# MCU_main_2.net
KiCad netlist of a schematic drawn in Altium Designer
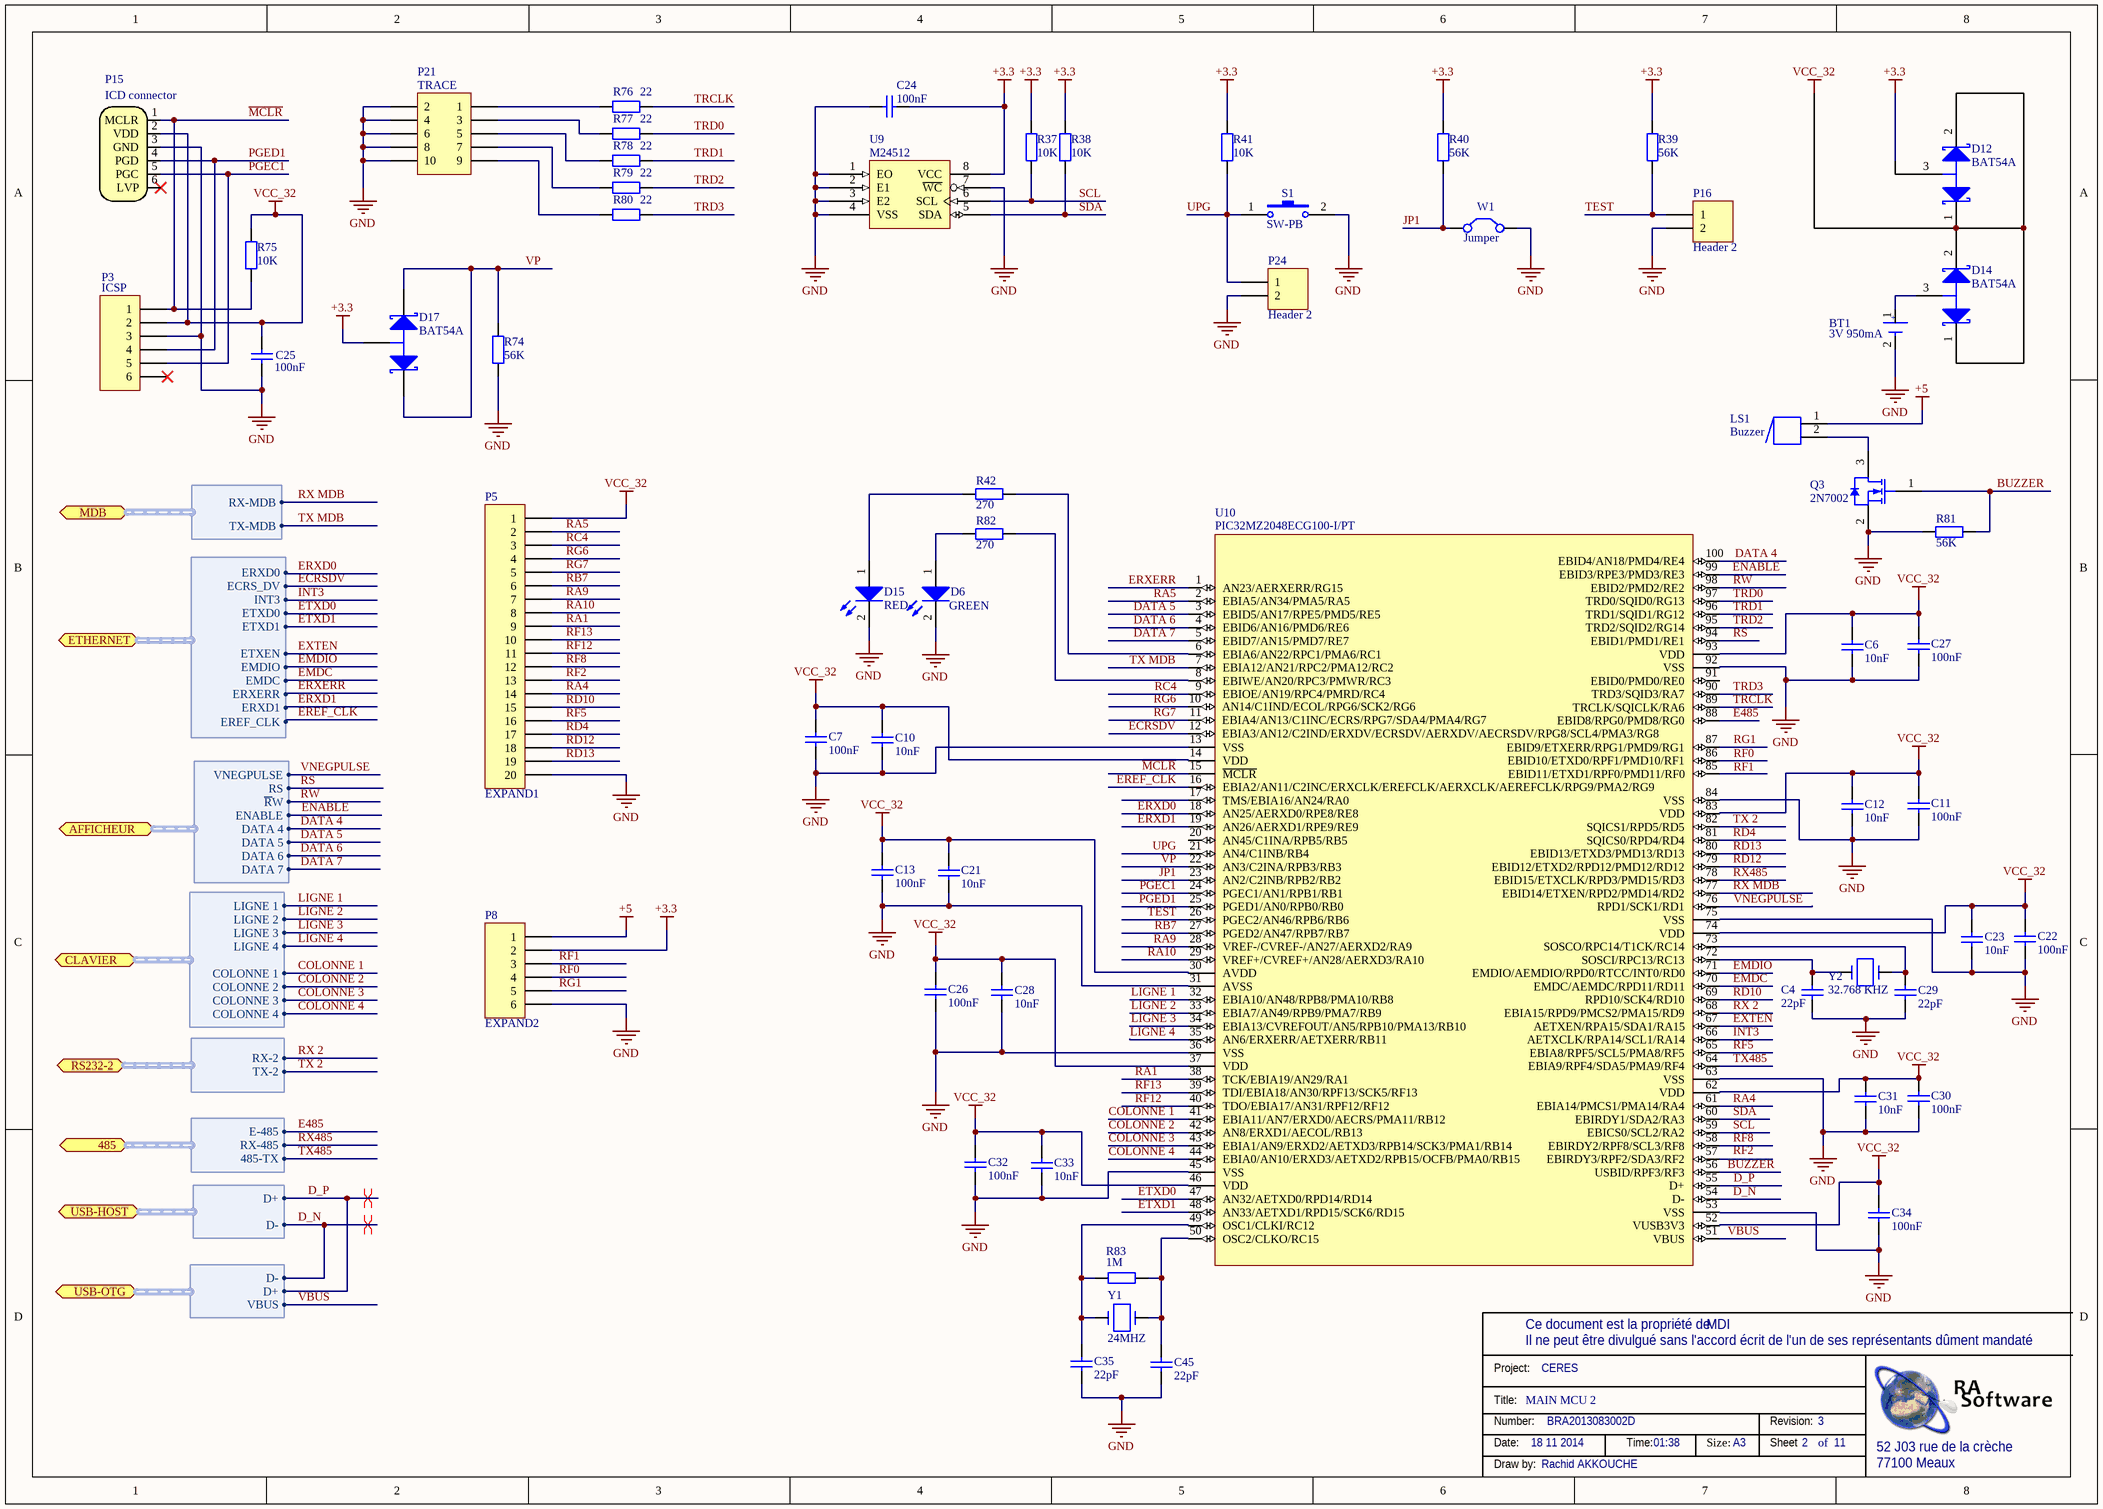
[diagram p0: MCU main_2.SchDoc]

(export (version "E")
  (design (tool "Eeschema 10.0.6"))
  (components
    (comp (ref "BT1")
      (value "3V 950mA")
      (footprint "CR2477+SMTU")
      (fields (field (name "MANUFACTURER") "RENATA") (field (name "MANUFACTURER PART NUMBER") "CR2477N"))
      (libsource (lib "UTIL_Library") (part "Batterie"))
    )
    (comp (ref "C4")
      (value "22pF")
      (footprint "C0805")
      (description "Capacitor")
      (fields
        (field (name "MANUFACTURER") "YAGEO")
        (field (name "MANUFACTURER PART NUMBER") "CC0805JRNPO9BN220")
      )
      (libsource (lib "BRA") (part "Cap 0805 22pF"))
    )
    (comp (ref "C6")
      (value "10nF")
      (footprint "C0805")
      (description "Capacitor")
      (fields (field (name "MANUFACTURER") "AVX") (field (name "MANUFACTURER PART NUMBER") "0402YC103KAT2A"))
      (libsource (lib "BRA") (part "Cap 0805 10nF"))
    )
    (comp (ref "C7")
      (value "100nF")
      (footprint "C0805")
      (description "Capacitor")
      (fields
        (field (name "MANUFACTURER") "MULTICOMP")
        (field (name "MANUFACTURER PART NUMBER") "MCCA000296")
      )
      (libsource (lib "BRA") (part "Cap 0805 100nF"))
    )
    (comp (ref "C10")
      (value "10nF")
      (footprint "C0805")
      (description "Capacitor")
      (fields (field (name "MANUFACTURER") "AVX") (field (name "MANUFACTURER PART NUMBER") "0402YC103KAT2A"))
      (libsource (lib "BRA") (part "Cap 0805 10nF"))
    )
    (comp (ref "C11")
      (value "100nF")
      (footprint "C0805")
      (description "Capacitor")
      (fields
        (field (name "MANUFACTURER") "MULTICOMP")
        (field (name "MANUFACTURER PART NUMBER") "MCCA000296")
      )
      (libsource (lib "BRA") (part "Cap 0805 100nF"))
    )
    (comp (ref "C12")
      (value "10nF")
      (footprint "C0805")
      (description "Capacitor")
      (fields (field (name "MANUFACTURER") "AVX") (field (name "MANUFACTURER PART NUMBER") "0402YC103KAT2A"))
      (libsource (lib "BRA") (part "Cap 0805 10nF"))
    )
    (comp (ref "C13")
      (value "100nF")
      (footprint "C0805")
      (description "Capacitor")
      (fields
        (field (name "MANUFACTURER") "MULTICOMP")
        (field (name "MANUFACTURER PART NUMBER") "MCCA000296")
      )
      (libsource (lib "BRA") (part "Cap 0805 100nF"))
    )
    (comp (ref "C21")
      (value "10nF")
      (footprint "C0805")
      (description "Capacitor")
      (fields (field (name "MANUFACTURER") "AVX") (field (name "MANUFACTURER PART NUMBER") "0402YC103KAT2A"))
      (libsource (lib "BRA") (part "Cap 0805 10nF"))
    )
    (comp (ref "C22")
      (value "100nF")
      (footprint "C0805")
      (description "Capacitor")
      (fields
        (field (name "MANUFACTURER") "MULTICOMP")
        (field (name "MANUFACTURER PART NUMBER") "MCCA000296")
      )
      (libsource (lib "BRA") (part "Cap 0805 100nF"))
    )
    (comp (ref "C23")
      (value "10nF")
      (footprint "C0805")
      (description "Capacitor")
      (fields (field (name "MANUFACTURER") "AVX") (field (name "MANUFACTURER PART NUMBER") "0402YC103KAT2A"))
      (libsource (lib "BRA") (part "Cap 0805 10nF"))
    )
    (comp (ref "C24")
      (value "100nF")
      (footprint "C0805")
      (description "Capacitor")
      (fields
        (field (name "MANUFACTURER") "MULTICOMP")
        (field (name "MANUFACTURER PART NUMBER") "MCCA000296")
      )
      (libsource (lib "BRA") (part "Cap 0805 100nF"))
    )
    (comp (ref "C25")
      (value "100nF")
      (footprint "C0805")
      (description "Capacitor")
      (fields
        (field (name "MANUFACTURER") "MULTICOMP")
        (field (name "MANUFACTURER PART NUMBER") "MCCA000296")
      )
      (libsource (lib "BRA") (part "Cap 0805 100nF"))
    )
    (comp (ref "C26")
      (value "100nF")
      (footprint "C0805")
      (description "Capacitor")
      (fields
        (field (name "MANUFACTURER") "MULTICOMP")
        (field (name "MANUFACTURER PART NUMBER") "MCCA000296")
      )
      (libsource (lib "BRA") (part "Cap 0805 100nF"))
    )
    (comp (ref "C27")
      (value "100nF")
      (footprint "C0805")
      (description "Capacitor")
      (fields
        (field (name "MANUFACTURER") "MULTICOMP")
        (field (name "MANUFACTURER PART NUMBER") "MCCA000296")
      )
      (libsource (lib "BRA") (part "Cap 0805 100nF"))
    )
    (comp (ref "C28")
      (value "10nF")
      (footprint "C0805")
      (description "Capacitor")
      (fields (field (name "MANUFACTURER") "AVX") (field (name "MANUFACTURER PART NUMBER") "0402YC103KAT2A"))
      (libsource (lib "BRA") (part "Cap 0805 10nF"))
    )
    (comp (ref "C29")
      (value "22pF")
      (footprint "C0805")
      (description "Capacitor")
      (fields
        (field (name "MANUFACTURER") "YAGEO")
        (field (name "MANUFACTURER PART NUMBER") "CC0805JRNPO9BN220")
      )
      (libsource (lib "BRA") (part "Cap 0805 22pF"))
    )
    (comp (ref "C30")
      (value "100nF")
      (footprint "C0805")
      (description "Capacitor")
      (fields
        (field (name "MANUFACTURER") "MULTICOMP")
        (field (name "MANUFACTURER PART NUMBER") "MCCA000296")
      )
      (libsource (lib "BRA") (part "Cap 0805 100nF"))
    )
    (comp (ref "C31")
      (value "10nF")
      (footprint "C0805")
      (description "Capacitor")
      (fields (field (name "MANUFACTURER") "AVX") (field (name "MANUFACTURER PART NUMBER") "0402YC103KAT2A"))
      (libsource (lib "BRA") (part "Cap 0805 10nF"))
    )
    (comp (ref "C32")
      (value "100nF")
      (footprint "C0805")
      (description "Capacitor")
      (fields
        (field (name "MANUFACTURER") "MULTICOMP")
        (field (name "MANUFACTURER PART NUMBER") "MCCA000296")
      )
      (libsource (lib "BRA") (part "Cap 0805 100nF"))
    )
    (comp (ref "C33")
      (value "10nF")
      (footprint "C0805")
      (description "Capacitor")
      (fields (field (name "MANUFACTURER") "AVX") (field (name "MANUFACTURER PART NUMBER") "0402YC103KAT2A"))
      (libsource (lib "BRA") (part "Cap 0805 10nF"))
    )
    (comp (ref "C34")
      (value "100nF")
      (footprint "C0805")
      (description "Capacitor")
      (fields
        (field (name "MANUFACTURER") "MULTICOMP")
        (field (name "MANUFACTURER PART NUMBER") "MCCA000296")
      )
      (libsource (lib "BRA") (part "Cap 0805 100nF"))
    )
    (comp (ref "C35")
      (value "22pF")
      (footprint "C0805")
      (description "Capacitor")
      (fields
        (field (name "MANUFACTURER") "YAGEO")
        (field (name "MANUFACTURER PART NUMBER") "CC0805JRNPO9BN220")
      )
      (libsource (lib "BRA") (part "Cap 0805 22pF"))
    )
    (comp (ref "C45")
      (value "22pF")
      (footprint "C0805")
      (description "Capacitor")
      (fields
        (field (name "MANUFACTURER") "YAGEO")
        (field (name "MANUFACTURER PART NUMBER") "CC0805JRNPO9BN220")
      )
      (libsource (lib "BRA") (part "Cap 0805 22pF"))
    )
    (comp (ref "D6")
      (value "HSMG-C191")
      (footprint "SYLANN:0603-LEDR")
      (description "Surface Mount Chip LED, Green")
      (fields (field (name "COULEUR") "GREEN"))
      (libsource (lib "Avago Optoelectronic LED") (part "HSMH-C190"))
    )
    (comp (ref "D12")
      (value "BAT54A")
      (footprint "SOT23")
      (description "Schottky Barrier Double Diode")
      (fields (field (name "MANUFACTURER") "FAIRCHILD SEMICONDUCTOR"))
      (libsource (lib "Philips Discrete Diode - Schottky") (part "BAT54A"))
    )
    (comp (ref "D14")
      (value "BAT54A")
      (footprint "SOT23")
      (description "Schottky Barrier Double Diode")
      (fields (field (name "MANUFACTURER") "FAIRCHILD SEMICONDUCTOR"))
      (libsource (lib "Philips Discrete Diode - Schottky") (part "BAT54A"))
    )
    (comp (ref "D15")
      (value "HSMH-C190")
      (footprint "SYLANN:0603-LEDR")
      (description "Surface Mount Chip LED, Red")
      (fields
        (field (name "MANUFACTURER") "AVAGO TECHNOLOGIES")
        (field (name "MANUFACTURER PART NUMBER") "HSMH-C190.")
        (field (name "COULEUR") "RED")
        (field (name "LONGUEUR/HAUTEUR") "1.6")
      )
      (libsource (lib "Avago Optoelectronic LED") (part "HSMH-C190"))
    )
    (comp (ref "D17")
      (value "BAT54A")
      (footprint "SOT23")
      (description "Schottky Barrier Double Diode")
      (fields (field (name "MANUFACTURER") "FAIRCHILD SEMICONDUCTOR"))
      (libsource (lib "") (part "BAT54A_1"))
    )
    (comp (ref "LS1")
      (value "Buzzer")
      (footprint "Buzzer ABI-017-RC")
      (description "Magnetic Transducer Buzzer")
      (fields
        (field (name "MANUFACTURER") "PRO SIGNAL")
        (field (name "MANUFACTURER PART NUMBER") "ABI-017-RC")
        (field (name "HAUTEUR, DIMENSION EXTERNE") "12.8")
        (field (name "HAUTEUR") "12.8")
        (field (name "LONGUEUR/HAUTEUR") "12.8")
      )
      (libsource (lib "Miscellaneous Devices") (part "Buzzer"))
    )
    (comp (ref "P3")
      (value "M20-8770642")
      (footprint "M20_1X6")
      (description "Header, 6-Pin")
      (fields (field (name "MANUFACTURER") "HARWIN") (field (name "ALTIUM_UNNAMED_1") "ICSP"))
      (libsource (lib "Miscellaneous Connectors") (part "Header 6"))
    )
    (comp (ref "P5")
      (value "EXPAND1")
      (footprint "M20-2X10")
      (description "Header, 20-Pin")
      (fields (field (name "PUBLISHER") "Altium Limited"))
      (libsource (lib "Miscellaneous Connectors") (part "Header 20"))
    )
    (comp (ref "P8")
      (value "EXPAND2")
      (footprint "M20_1X6")
      (description "Header, 6-Pin")
      (fields (field (name "PUBLISHER") "Altium Limited"))
      (libsource (lib "Miscellaneous Connectors") (part "Header 6"))
    )
    (comp (ref "P15")
      (value "ICD connector")
      (footprint "TC2030")
      (description "Conector par ICD")
      (libsource (lib "TC2030") (part "TC2030-MCP-NL"))
    )
    (comp (ref "P16")
      (value "Header 2")
      (footprint "M20_1X2")
      (description "Header, 2-Pin")
      (fields
        (field (name "MANUFACTURER") "HARWIN")
        (field (name "MANUFACTURER PART NUMBER") "M20-8770242")
        (field (name "PUBLISHER") "Altium Limited")
      )
      (libsource (lib "Miscellaneous Connectors") (part "Header 2"))
    )
    (comp (ref "P21")
      (value "M20-8760542")
      (footprint "HE10_10PTS_CMS")
      (description "Header, 5-Pin, Dual row")
      (fields (field (name "ALTIUM_UNNAMED_1") "TRACE") (field (name "MANUFACTURER") "HARWIN"))
      (libsource (lib "Miscellaneous Connectors") (part "Header 5X2"))
    )
    (comp (ref "P24")
      (value "Header 2")
      (footprint "M20_1X2")
      (description "Header, 2-Pin")
      (fields
        (field (name "MANUFACTURER") "HARWIN")
        (field (name "MANUFACTURER PART NUMBER") "M20-8770242")
        (field (name "PUBLISHER") "Altium Limited")
      )
      (libsource (lib "Miscellaneous Connectors") (part "Header 2"))
    )
    (comp (ref "Q3")
      (value "2N7002")
      (footprint "SOT23")
      (description "N-channel Enhancement Mode Field-effect Transistor")
      (fields (field (name "MANUFACTURER") "STMICROELECTRONICS") (field (name "PUBLISHER") "Altium Limited"))
      (libsource (lib "Philips Discrete MOSFET - Low Power") (part "2N7002"))
    )
    (comp (ref "R37")
      (value "10K")
      (footprint "R0805")
      (description "Resistor")
      (fields
        (field (name "MANUFACTURER") "MULTICOMP")
        (field (name "MANUFACTURER PART NUMBER") "MC0.1W08051%10KFR")
      )
      (libsource (lib "BRA") (part "Resistor 0805 10K"))
    )
    (comp (ref "R38")
      (value "10K")
      (footprint "R0805")
      (description "Resistor")
      (fields
        (field (name "MANUFACTURER") "MULTICOMP")
        (field (name "MANUFACTURER PART NUMBER") "MC0.1W08051%10KFR")
      )
      (libsource (lib "BRA") (part "Resistor 0805 10K"))
    )
    (comp (ref "R39")
      (value "56K")
      (footprint "R0805")
      (description "Resistor")
      (fields
        (field (name "MANUFACTURER") "MULTICOMP")
        (field (name "MANUFACTURER PART NUMBER") "MC0.1W08051%56KFR")
      )
      (libsource (lib "BRA") (part "Resistor 0805 56K"))
    )
    (comp (ref "R40")
      (value "56K")
      (footprint "R0805")
      (description "Resistor")
      (fields
        (field (name "MANUFACTURER") "MULTICOMP")
        (field (name "MANUFACTURER PART NUMBER") "MC0.1W08051%56KFR")
      )
      (libsource (lib "BRA") (part "Resistor 0805 56K"))
    )
    (comp (ref "R41")
      (value "10K")
      (footprint "R0805")
      (description "Resistor")
      (fields
        (field (name "MANUFACTURER") "MULTICOMP")
        (field (name "MANUFACTURER PART NUMBER") "MC0.1W08051%10KFR")
      )
      (libsource (lib "BRA") (part "Resistor 0805 10K"))
    )
    (comp (ref "R42")
      (value "270")
      (footprint "R0805")
      (description "Resistor")
      (fields
        (field (name "MANUFACTURER") "MULTICOMP")
        (field (name "MANUFACTURER PART NUMBER") "MC0.1W08051%1KFR")
      )
      (libsource (lib "BRA") (part "Resistor 0805 1K"))
    )
    (comp (ref "R74")
      (value "56K")
      (footprint "R0805")
      (description "Resistor")
      (fields
        (field (name "MANUFACTURER") "MULTICOMP")
        (field (name "MANUFACTURER PART NUMBER") "MC0.1W08051%56KFR")
      )
      (libsource (lib "") (part "Resistor 0805 56K_1"))
    )
    (comp (ref "R75")
      (value "10K")
      (footprint "R0805")
      (description "Resistor")
      (fields
        (field (name "MANUFACTURER") "MULTICOMP")
        (field (name "MANUFACTURER PART NUMBER") "MC0.1W08051%10KFR")
      )
      (libsource (lib "BRA") (part "Resistor 0805 10K"))
    )
    (comp (ref "R76")
      (value "22")
      (footprint "R0805")
      (description "Resistor")
      (fields
        (field (name "MANUFACTURER") "MULTICOMP")
        (field (name "MANUFACTURER PART NUMBER") "MC01W0805122R")
      )
      (libsource (lib "BRA") (part "Resistor 0805 22"))
    )
    (comp (ref "R77")
      (value "22")
      (footprint "R0805")
      (description "Resistor")
      (fields
        (field (name "MANUFACTURER") "MULTICOMP")
        (field (name "MANUFACTURER PART NUMBER") "MC01W0805122R")
      )
      (libsource (lib "BRA") (part "Resistor 0805 22"))
    )
    (comp (ref "R78")
      (value "22")
      (footprint "R0805")
      (description "Resistor")
      (fields
        (field (name "MANUFACTURER") "MULTICOMP")
        (field (name "MANUFACTURER PART NUMBER") "MC01W0805122R")
      )
      (libsource (lib "BRA") (part "Resistor 0805 22"))
    )
    (comp (ref "R79")
      (value "22")
      (footprint "R0805")
      (description "Resistor")
      (fields
        (field (name "MANUFACTURER") "MULTICOMP")
        (field (name "MANUFACTURER PART NUMBER") "MC01W0805122R")
      )
      (libsource (lib "BRA") (part "Resistor 0805 22"))
    )
    (comp (ref "R80")
      (value "22")
      (footprint "R0805")
      (description "Resistor")
      (fields
        (field (name "MANUFACTURER") "MULTICOMP")
        (field (name "MANUFACTURER PART NUMBER") "MC01W0805122R")
      )
      (libsource (lib "BRA") (part "Resistor 0805 22"))
    )
    (comp (ref "R81")
      (value "56K")
      (footprint "R0805")
      (description "Resistor")
      (fields
        (field (name "MANUFACTURER") "MULTICOMP")
        (field (name "MANUFACTURER PART NUMBER") "MC0.1W08051%56KFR")
      )
      (libsource (lib "BRA") (part "Resistor 0805 56K"))
    )
    (comp (ref "R82")
      (value "270")
      (footprint "R0805")
      (description "Resistor")
      (fields
        (field (name "MANUFACTURER") "MULTICOMP")
        (field (name "MANUFACTURER PART NUMBER") "MC0.1W08051%1KFR")
      )
      (libsource (lib "BRA") (part "Resistor 0805 1K"))
    )
    (comp (ref "R83")
      (value "1M")
      (footprint "R0805")
      (description "Resistor")
      (libsource (lib "BRA") (part "Resistor 0805 1M"))
    )
    (comp (ref "S1")
      (value "SW-PB")
      (footprint "EVQQ2Y03W")
      (description "Switch")
      (fields
        (field (name "MANUFACTURER") "PANASONIC")
        (field (name "MANUFACTURER PART NUMBER") "EVQQ2Y03W")
        (field (name "PUBLISHER") "Altium Limited")
      )
      (libsource (lib "Miscellaneous Devices") (part "SW-PB"))
    )
    (comp (ref "U9")
      (value "M24512")
      (footprint "SOIC8")
      (description "EEPROM 512K I2C")
      (fields
        (field (name "MANUFACTURER") "STMICROELECTRONICS")
        (field (name "MANUFACTURER PART NUMBER") "M24512-WMN6P")
      )
      (libsource (lib "BRA") (part "M24512-MN"))
    )
    (comp (ref "U10")
      (value "PIC32MZ2048ECG100-I/PT")
      (footprint "TQFP100pt")
      (description "PIC32MZ2048ECG100")
      (fields (field (name "MANUFACTURER") "Microchip Technology"))
      (libsource (lib "BRA") (part "PIC32MZ Embedded Connectivity"))
    )
    (comp (ref "W1")
      (value "Jumper")
      (footprint "M20_1X2")
      (description "Jumper Wire")
      (fields
        (field (name "MANUFACTURER") "HARWIN")
        (field (name "MANUFACTURER PART NUMBER") "M20-8770242")
        (field (name "PUBLISHER") "Altium Limited")
      )
      (libsource (lib "Miscellaneous Devices") (part "Jumper"))
    )
    (comp (ref "Y1")
      (value "24MHZ")
      (footprint "HC49SD")
      (description "QUARTZ 24MHZ")
      (fields (field (name "MANUFACTURER") "YIC"))
      (libsource (lib "BRA") (part "CRYSTAL 24MHZ"))
    )
    (comp (ref "Y2")
      (value "32.768 KHZ")
      (footprint "86SMX")
      (fields
        (field (name "MANUFACTURER") "FOX ELECTRONICS")
        (field (name "MANUFACTURER PART NUMBER") "FPXLF080-20")
      )
      (libsource (lib "UTIL_Library") (part "CRYSTAL2"))
    )
  )
  (nets
    (net (code "10") (name "+3.3") (class "Default")
      (node (ref "C24") (pin "1") (pinfunction "1_1") (pintype "passive"))
      (node (ref "D12") (pin "3") (pinfunction "A_3") (pintype "passive"))
      (node (ref "D17") (pin "3") (pinfunction "A_3") (pintype "passive"))
      (node (ref "P8") (pin "2") (pinfunction "2_2") (pintype "passive"))
      (node (ref "R37") (pin "2") (pinfunction "2_2") (pintype "passive"))
      (node (ref "R38") (pin "2") (pinfunction "2_2") (pintype "passive"))
      (node (ref "R39") (pin "2") (pinfunction "2_2") (pintype "passive"))
      (node (ref "R40") (pin "2") (pinfunction "2_2") (pintype "passive"))
      (node (ref "R41") (pin "2") (pinfunction "2_2") (pintype "passive"))
      (node (ref "U9") (pin "8") (pinfunction "VCC_8") (pintype "power_in"))
    )
    (net (code "11") (name "+5") (class "Default")
      (node (ref "LS1") (pin "1") (pinfunction "1_1") (pintype "passive"))
      (node (ref "P8") (pin "1") (pinfunction "1_1") (pintype "passive"))
    )
    (net (code "12") (name "/BUZZER") (class "Default")
      (node (ref "Q3") (pin "1") (pinfunction "G_1") (pintype "passive"))
      (node (ref "R81") (pin "2") (pinfunction "2_2") (pintype "passive"))
      (node (ref "U10") (pin "56") (pinfunction "USBID/RPF3/RF3_56") (pintype "bidirectional"))
    )
    (net (code "13") (name "/COLONNE 1") (class "Default")
      (node (ref "U10") (pin "41") (pinfunction "EBIA11/AN7/ERXD0/AECRS/PMA11/RB12_41") (pintype "bidirectional"))
    )
    (net (code "14") (name "/COLONNE 2") (class "Default")
      (node (ref "U10") (pin "42") (pinfunction "AN8/ERXD1/AECOL/RB13_42") (pintype "bidirectional"))
    )
    (net (code "15") (name "/COLONNE 3") (class "Default")
      (node (ref "U10") (pin "43") (pinfunction "EBIA1/AN9/ERXD2/AETXD3/RPB14/SCK3/PMA1/RB14_43") (pintype "bidirectional"))
    )
    (net (code "16") (name "/COLONNE 4") (class "Default")
      (node (ref "U10") (pin "44") (pinfunction "EBIA0/AN10/ERXD3/AETXD2/RPB15/OCFB/PMA0/RB15_44") (pintype "bidirectional"))
    )
    (net (code "17") (name "/DATA 4") (class "Default")
      (node (ref "U10") (pin "100") (pinfunction "EBID4/AN18/PMD4/RE4_100") (pintype "bidirectional"))
    )
    (net (code "18") (name "/DATA 5") (class "Default")
      (node (ref "U10") (pin "3") (pinfunction "EBID5/AN17/RPE5/PMD5/RE5_3") (pintype "bidirectional"))
    )
    (net (code "19") (name "/DATA 6") (class "Default")
      (node (ref "U10") (pin "4") (pinfunction "EBID6/AN16/PMD6/RE6_4") (pintype "bidirectional"))
    )
    (net (code "20") (name "/DATA 7") (class "Default")
      (node (ref "U10") (pin "5") (pinfunction "EBID7/AN15/PMD7/RE7_5") (pintype "bidirectional"))
    )
    (net (code "21") (name "/D_N") (class "Default")
      (node (ref "U10") (pin "54") (pinfunction "D-_54") (pintype "bidirectional"))
    )
    (net (code "22") (name "/D_P") (class "Default")
      (node (ref "U10") (pin "55") (pinfunction "D+_55") (pintype "bidirectional"))
    )
    (net (code "23") (name "/E485") (class "Default")
      (node (ref "U10") (pin "88") (pinfunction "EBID8/RPG0/PMD8/RG0_88") (pintype "bidirectional"))
    )
    (net (code "24") (name "/ECRSDV") (class "Default")
      (node (ref "U10") (pin "12") (pinfunction "EBIA3/AN12/C2IND/ERXDV/ECRSDV/AERXDV/AECRSDV/RPG8/SCL4/PMA3/RG8_12") (pintype "bidirectional"))
    )
    (net (code "25") (name "/EMDC") (class "Default")
      (node (ref "U10") (pin "70") (pinfunction "EMDC/AEMDC/RPD11/RD11_70") (pintype "bidirectional"))
    )
    (net (code "26") (name "/EMDIO") (class "Default")
      (node (ref "U10") (pin "71") (pinfunction "EMDIO/AEMDIO/RPD0/RTCC/INT0/RD0_71") (pintype "bidirectional"))
    )
    (net (code "27") (name "/ENABLE") (class "Default")
      (node (ref "U10") (pin "99") (pinfunction "EBID3/RPE3/PMD3/RE3_99") (pintype "bidirectional"))
    )
    (net (code "28") (name "/EREF_CLK") (class "Default")
      (node (ref "U10") (pin "16") (pinfunction "EBIA2/AN11/C2INC/ERXCLK/EREFCLK/AERXCLK/AEREFCLK/RPG9/PMA2/RG9_16") (pintype "bidirectional"))
    )
    (net (code "29") (name "/ERXD0") (class "Default")
      (node (ref "U10") (pin "18") (pinfunction "AN25/AERXD0/RPE8/RE8_18") (pintype "bidirectional"))
    )
    (net (code "30") (name "/ERXD1") (class "Default")
      (node (ref "U10") (pin "19") (pinfunction "AN26/AERXD1/RPE9/RE9_19") (pintype "bidirectional"))
    )
    (net (code "31") (name "/ERXERR") (class "Default")
      (node (ref "U10") (pin "1") (pinfunction "AN23/AERXERR/RG15_1") (pintype "bidirectional"))
    )
    (net (code "32") (name "/ETXD0") (class "Default")
      (node (ref "U10") (pin "47") (pinfunction "AN32/AETXD0/RPD14/RD14_47") (pintype "bidirectional"))
    )
    (net (code "33") (name "/ETXD1") (class "Default")
      (node (ref "U10") (pin "48") (pinfunction "AN33/AETXD1/RPD15/SCK6/RD15_48") (pintype "bidirectional"))
    )
    (net (code "34") (name "/EXTEN") (class "Default")
      (node (ref "U10") (pin "67") (pinfunction "AETXEN/RPA15/SDA1/RA15_67") (pintype "bidirectional"))
    )
    (net (code "35") (name "/INT3") (class "Default")
      (node (ref "U10") (pin "66") (pinfunction "AETXCLK/RPA14/SCL1/RA14_66") (pintype "bidirectional"))
    )
    (net (code "36") (name "/JP1") (class "Default")
      (node (ref "R40") (pin "1") (pinfunction "1_1") (pintype "passive"))
      (node (ref "U10") (pin "23") (pinfunction "AN2/C2INB/RPB2/RB2_23") (pintype "bidirectional"))
      (node (ref "W1") (pin "1") (pinfunction "C1_1") (pintype "passive"))
    )
    (net (code "37") (name "/LIGNE 1") (class "Default")
      (node (ref "U10") (pin "32") (pinfunction "EBIA10/AN48/RPB8/PMA10/RB8_32") (pintype "bidirectional"))
    )
    (net (code "38") (name "/LIGNE 2") (class "Default")
      (node (ref "U10") (pin "33") (pinfunction "EBIA7/AN49/RPB9/PMA7/RB9_33") (pintype "bidirectional"))
    )
    (net (code "39") (name "/LIGNE 3") (class "Default")
      (node (ref "U10") (pin "34") (pinfunction "EBIA13/CVREFOUT/AN5/RPB10/PMA13/RB10_34") (pintype "bidirectional"))
    )
    (net (code "40") (name "/LIGNE 4") (class "Default")
      (node (ref "U10") (pin "35") (pinfunction "AN6/ERXERR/AETXERR/RB11_35") (pintype "bidirectional"))
    )
    (net (code "41") (name "/PGEC1") (class "Default")
      (node (ref "P15") (pin "5") (pinfunction "PGC_5") (pintype "passive"))
      (node (ref "P3") (pin "5") (pinfunction "5_5") (pintype "passive"))
      (node (ref "U10") (pin "24") (pinfunction "PGEC1/AN1/RPB1/RB1_24") (pintype "bidirectional"))
    )
    (net (code "42") (name "/PGED1") (class "Default")
      (node (ref "P15") (pin "4") (pinfunction "PGD_4") (pintype "passive"))
      (node (ref "P3") (pin "4") (pinfunction "4_4") (pintype "passive"))
      (node (ref "U10") (pin "25") (pinfunction "PGED1/AN0/RPB0/RB0_25") (pintype "bidirectional"))
    )
    (net (code "43") (name "/RA1") (class "Default")
      (node (ref "P5") (pin "9") (pinfunction "9_9") (pintype "passive"))
      (node (ref "U10") (pin "38") (pinfunction "TCK/EBIA19/AN29/RA1_38") (pintype "bidirectional"))
    )
    (net (code "44") (name "/RA4") (class "Default")
      (node (ref "P5") (pin "14") (pinfunction "14_14") (pintype "passive"))
      (node (ref "U10") (pin "61") (pinfunction "EBIA14/PMCS1/PMA14/RA4_61") (pintype "bidirectional"))
    )
    (net (code "45") (name "/RA5") (class "Default")
      (node (ref "P5") (pin "2") (pinfunction "2_2") (pintype "passive"))
      (node (ref "U10") (pin "2") (pinfunction "EBIA5/AN34/PMA5/RA5_2") (pintype "bidirectional"))
    )
    (net (code "46") (name "/RA9") (class "Default")
      (node (ref "P5") (pin "7") (pinfunction "7_7") (pintype "passive"))
      (node (ref "U10") (pin "28") (pinfunction "VREF-/CVREF-/AN27/AERXD2/RA9_28") (pintype "bidirectional"))
    )
    (net (code "47") (name "/RA10") (class "Default")
      (node (ref "P5") (pin "8") (pinfunction "8_8") (pintype "passive"))
      (node (ref "U10") (pin "29") (pinfunction "VREF+/CVREF+/AN28/AERXD3/RA10_29") (pintype "bidirectional"))
    )
    (net (code "48") (name "/RB7") (class "Default")
      (node (ref "P5") (pin "6") (pinfunction "6_6") (pintype "passive"))
      (node (ref "U10") (pin "27") (pinfunction "PGED2/AN47/RPB7/RB7_27") (pintype "bidirectional"))
    )
    (net (code "49") (name "/RC4") (class "Default")
      (node (ref "P5") (pin "3") (pinfunction "3_3") (pintype "passive"))
      (node (ref "U10") (pin "9") (pinfunction "EBIOE/AN19/RPC4/PMRD/RC4_9") (pintype "bidirectional"))
    )
    (net (code "50") (name "/RD4") (class "Default")
      (node (ref "P5") (pin "17") (pinfunction "17_17") (pintype "passive"))
      (node (ref "U10") (pin "81") (pinfunction "SQICS0/RPD4/RD4_81") (pintype "bidirectional"))
    )
    (net (code "51") (name "/RD10") (class "Default")
      (node (ref "P5") (pin "15") (pinfunction "15_15") (pintype "passive"))
      (node (ref "U10") (pin "69") (pinfunction "RPD10/SCK4/RD10_69") (pintype "bidirectional"))
    )
    (net (code "52") (name "/RD12") (class "Default")
      (node (ref "P5") (pin "18") (pinfunction "18_18") (pintype "passive"))
      (node (ref "U10") (pin "79") (pinfunction "EBID12/ETXD2/RPD12/PMD12/RD12_79") (pintype "bidirectional"))
    )
    (net (code "53") (name "/RD13") (class "Default")
      (node (ref "P5") (pin "19") (pinfunction "19_19") (pintype "passive"))
      (node (ref "U10") (pin "80") (pinfunction "EBID13/ETXD3/PMD13/RD13_80") (pintype "bidirectional"))
    )
    (net (code "54") (name "/RF0") (class "Default")
      (node (ref "P8") (pin "4") (pinfunction "4_4") (pintype "passive"))
    )
    (net (code "55") (name "/RF1") (class "Default")
      (node (ref "P8") (pin "3") (pinfunction "3_3") (pintype "passive"))
    )
    (net (code "56") (name "/RF2") (class "Default")
      (node (ref "P5") (pin "13") (pinfunction "13_13") (pintype "passive"))
    )
    (net (code "57") (name "/RF5") (class "Default")
      (node (ref "P5") (pin "16") (pinfunction "16_16") (pintype "passive"))
      (node (ref "U10") (pin "65") (pinfunction "EBIA8/RPF5/SCL5/PMA8/RF5_65") (pintype "bidirectional"))
    )
    (net (code "58") (name "/RF8") (class "Default")
      (node (ref "P5") (pin "12") (pinfunction "12_12") (pintype "passive"))
      (node (ref "U10") (pin "58") (pinfunction "EBIRDY2/RPF8/SCL3/RF8_58") (pintype "bidirectional"))
    )
    (net (code "59") (name "/RF12") (class "Default")
      (node (ref "P5") (pin "11") (pinfunction "11_11") (pintype "passive"))
      (node (ref "U10") (pin "40") (pinfunction "TDO/EBIA17/AN31/RPF12/RF12_40") (pintype "bidirectional"))
    )
    (net (code "60") (name "/RF13") (class "Default")
      (node (ref "P5") (pin "10") (pinfunction "10_10") (pintype "passive"))
      (node (ref "U10") (pin "39") (pinfunction "TDI/EBIA18/AN30/RPF13/SCK5/RF13_39") (pintype "bidirectional"))
    )
    (net (code "61") (name "/RG1") (class "Default")
      (node (ref "P8") (pin "5") (pinfunction "5_5") (pintype "passive"))
      (node (ref "U10") (pin "87") (pinfunction "EBID9/ETXERR/RPG1/PMD9/RG1_87") (pintype "bidirectional"))
    )
    (net (code "62") (name "/RG6") (class "Default")
      (node (ref "P5") (pin "4") (pinfunction "4_4") (pintype "passive"))
      (node (ref "U10") (pin "10") (pinfunction "AN14/C1IND/ECOL/RPG6/SCK2/RG6_10") (pintype "bidirectional"))
    )
    (net (code "63") (name "/RG7") (class "Default")
      (node (ref "P5") (pin "5") (pinfunction "5_5") (pintype "passive"))
      (node (ref "U10") (pin "11") (pinfunction "EBIA4/AN13/C1INC/ECRS/RPG7/SDA4/PMA4/RG7_11") (pintype "bidirectional"))
    )
    (net (code "64") (name "/RS") (class "Default")
      (node (ref "U10") (pin "94") (pinfunction "EBID1/PMD1/RE1_94") (pintype "bidirectional"))
    )
    (net (code "65") (name "/RX 2") (class "Default")
      (node (ref "U10") (pin "68") (pinfunction "EBIA15/RPD9/PMCS2/PMA15/RD9_68") (pintype "bidirectional"))
    )
    (net (code "66") (name "/RX MDB") (class "Default")
      (node (ref "U10") (pin "77") (pinfunction "EBID14/ETXEN/RPD2/PMD14/RD2_77") (pintype "bidirectional"))
    )
    (net (code "67") (name "/RX485") (class "Default")
      (node (ref "U10") (pin "78") (pinfunction "EBID15/ETXCLK/RPD3/PMD15/RD3_78") (pintype "bidirectional"))
    )
    (net (code "68") (name "/SCL") (class "Default")
      (node (ref "R37") (pin "1") (pinfunction "1_1") (pintype "passive"))
      (node (ref "U10") (pin "59") (pinfunction "EBICS0/SCL2/RA2_59") (pintype "bidirectional"))
      (node (ref "U9") (pin "6") (pinfunction "SCL_6") (pintype "input"))
    )
    (net (code "69") (name "/SDA") (class "Default")
      (node (ref "R38") (pin "1") (pinfunction "1_1") (pintype "passive"))
      (node (ref "U10") (pin "60") (pinfunction "EBIRDY1/SDA2/RA3_60") (pintype "bidirectional"))
      (node (ref "U9") (pin "5") (pinfunction "SDA_5") (pintype "bidirectional"))
    )
    (net (code "70") (name "/TEST") (class "Default")
      (node (ref "P16") (pin "1") (pinfunction "1_1") (pintype "passive"))
      (node (ref "R39") (pin "1") (pinfunction "1_1") (pintype "passive"))
      (node (ref "U10") (pin "26") (pinfunction "PGEC2/AN46/RPB6/RB6_26") (pintype "bidirectional"))
    )
    (net (code "71") (name "/TRCLK") (class "Default")
      (node (ref "R76") (pin "1") (pinfunction "1_1") (pintype "passive"))
      (node (ref "U10") (pin "89") (pinfunction "TRCLK/SQICLK/RA6_89") (pintype "bidirectional"))
    )
    (net (code "72") (name "/TRD0") (class "Default")
      (node (ref "R77") (pin "1") (pinfunction "1_1") (pintype "passive"))
      (node (ref "U10") (pin "97") (pinfunction "TRD0/SQID0/RG13_97") (pintype "bidirectional"))
    )
    (net (code "73") (name "/TRD1") (class "Default")
      (node (ref "R78") (pin "1") (pinfunction "1_1") (pintype "passive"))
      (node (ref "U10") (pin "96") (pinfunction "TRD1/SQID1/RG12_96") (pintype "bidirectional"))
    )
    (net (code "74") (name "/TRD2") (class "Default")
      (node (ref "R79") (pin "1") (pinfunction "1_1") (pintype "passive"))
      (node (ref "U10") (pin "95") (pinfunction "TRD2/SQID2/RG14_95") (pintype "bidirectional"))
    )
    (net (code "75") (name "/TRD3") (class "Default")
      (node (ref "R80") (pin "1") (pinfunction "1_1") (pintype "passive"))
      (node (ref "U10") (pin "90") (pinfunction "TRD3/SQID3/RA7_90") (pintype "bidirectional"))
    )
    (net (code "76") (name "/TX 2") (class "Default")
      (node (ref "U10") (pin "82") (pinfunction "SQICS1/RPD5/RD5_82") (pintype "bidirectional"))
    )
    (net (code "77") (name "/TX MDB") (class "Default")
      (node (ref "U10") (pin "7") (pinfunction "EBIA12/AN21/RPC2/PMA12/RC2_7") (pintype "bidirectional"))
    )
    (net (code "78") (name "/TX485") (class "Default")
      (node (ref "U10") (pin "64") (pinfunction "EBIA9/RPF4/SDA5/PMA9/RF4_64") (pintype "bidirectional"))
    )
    (net (code "79") (name "/UPG") (class "Default")
      (node (ref "P24") (pin "1") (pinfunction "1_1") (pintype "passive"))
      (node (ref "R41") (pin "1") (pinfunction "1_1") (pintype "passive"))
      (node (ref "S1") (pin "1") (pinfunction "1_1") (pintype "passive"))
      (node (ref "U10") (pin "21") (pinfunction "AN4/C1INB/RB4_21") (pintype "bidirectional"))
    )
    (net (code "80") (name "/VBUS") (class "Default")
      (node (ref "U10") (pin "51") (pinfunction "VBUS_51") (pintype "bidirectional"))
    )
    (net (code "81") (name "/VNEGPULSE") (class "Default")
      (node (ref "U10") (pin "76") (pinfunction "RPD1/SCK1/RD1_76") (pintype "bidirectional"))
    )
    (net (code "82") (name "/VP") (class "Default")
      (node (ref "D17") (pin "1") (pinfunction "K1_1") (pintype "passive"))
      (node (ref "D17") (pin "2") (pinfunction "K2_2") (pintype "passive"))
      (node (ref "R74") (pin "2") (pinfunction "2_2") (pintype "passive"))
      (node (ref "U10") (pin "22") (pinfunction "AN3/C2INA/RPB3/RB3_22") (pintype "bidirectional"))
    )
    (net (code "91") (name "/~{MCLR}") (class "Default")
      (node (ref "P15") (pin "1") (pinfunction "MCLR_1") (pintype "passive"))
      (node (ref "P3") (pin "1") (pinfunction "1_1") (pintype "passive"))
      (node (ref "R75") (pin "1") (pinfunction "1_1") (pintype "passive"))
      (node (ref "U10") (pin "15") (pinfunction "~{MCLR}_15") (pintype "power_in"))
    )
    (net (code "92") (name "/~{R}W") (class "Default")
      (node (ref "U10") (pin "98") (pinfunction "EBID2/PMD2/RE2_98") (pintype "bidirectional"))
    )
    (net (code "93") (name "GND") (class "Default")
      (node (ref "BT1") (pin "2") (pinfunction "2_2") (pintype "passive"))
      (node (ref "C10") (pin "1") (pinfunction "1_1") (pintype "passive"))
      (node (ref "C11") (pin "1") (pinfunction "1_1") (pintype "passive"))
      (node (ref "C12") (pin "1") (pinfunction "1_1") (pintype "passive"))
      (node (ref "C13") (pin "1") (pinfunction "1_1") (pintype "passive"))
      (node (ref "C21") (pin "1") (pinfunction "1_1") (pintype "passive"))
      (node (ref "C22") (pin "1") (pinfunction "1_1") (pintype "passive"))
      (node (ref "C23") (pin "1") (pinfunction "1_1") (pintype "passive"))
      (node (ref "C24") (pin "2") (pinfunction "2_2") (pintype "passive"))
      (node (ref "C25") (pin "1") (pinfunction "1_1") (pintype "passive"))
      (node (ref "C26") (pin "1") (pinfunction "1_1") (pintype "passive"))
      (node (ref "C27") (pin "1") (pinfunction "1_1") (pintype "passive"))
      (node (ref "C28") (pin "1") (pinfunction "1_1") (pintype "passive"))
      (node (ref "C29") (pin "2") (pinfunction "2_2") (pintype "passive"))
      (node (ref "C30") (pin "1") (pinfunction "1_1") (pintype "passive"))
      (node (ref "C31") (pin "1") (pinfunction "1_1") (pintype "passive"))
      (node (ref "C32") (pin "1") (pinfunction "1_1") (pintype "passive"))
      (node (ref "C33") (pin "1") (pinfunction "1_1") (pintype "passive"))
      (node (ref "C34") (pin "1") (pinfunction "1_1") (pintype "passive"))
      (node (ref "C35") (pin "2") (pinfunction "2_2") (pintype "passive"))
      (node (ref "C4") (pin "2") (pinfunction "2_2") (pintype "passive"))
      (node (ref "C45") (pin "2") (pinfunction "2_2") (pintype "passive"))
      (node (ref "C6") (pin "1") (pinfunction "1_1") (pintype "passive"))
      (node (ref "C7") (pin "1") (pinfunction "1_1") (pintype "passive"))
      (node (ref "D15") (pin "2") (pinfunction "K_2") (pintype "passive"))
      (node (ref "D6") (pin "2") (pinfunction "K_2") (pintype "passive"))
      (node (ref "P15") (pin "3") (pinfunction "GND_3") (pintype "passive"))
      (node (ref "P16") (pin "2") (pinfunction "2_2") (pintype "passive"))
      (node (ref "P21") (pin "10") (pinfunction "10_10") (pintype "passive"))
      (node (ref "P21") (pin "2") (pinfunction "2_2") (pintype "passive"))
      (node (ref "P21") (pin "4") (pinfunction "4_4") (pintype "passive"))
      (node (ref "P21") (pin "6") (pinfunction "6_6") (pintype "passive"))
      (node (ref "P21") (pin "8") (pinfunction "8_8") (pintype "passive"))
      (node (ref "P24") (pin "2") (pinfunction "2_2") (pintype "passive"))
      (node (ref "P3") (pin "3") (pinfunction "3_3") (pintype "passive"))
      (node (ref "P5") (pin "20") (pinfunction "20_20") (pintype "passive"))
      (node (ref "P8") (pin "6") (pinfunction "6_6") (pintype "passive"))
      (node (ref "Q3") (pin "2") (pinfunction "S_2") (pintype "passive"))
      (node (ref "R74") (pin "1") (pinfunction "1_1") (pintype "passive"))
      (node (ref "R81") (pin "1") (pinfunction "1_1") (pintype "passive"))
      (node (ref "S1") (pin "2") (pinfunction "2_2") (pintype "passive"))
      (node (ref "U10") (pin "13") (pinfunction "VSS_13") (pintype "power_in"))
      (node (ref "U10") (pin "31") (pinfunction "AVSS_31") (pintype "power_in"))
      (node (ref "U10") (pin "36") (pinfunction "VSS_36") (pintype "power_in"))
      (node (ref "U10") (pin "45") (pinfunction "VSS_45") (pintype "power_in"))
      (node (ref "U10") (pin "53") (pinfunction "VSS_53") (pintype "power_in"))
      (node (ref "U10") (pin "63") (pinfunction "VSS_63") (pintype "power_in"))
      (node (ref "U10") (pin "75") (pinfunction "VSS_75") (pintype "power_in"))
      (node (ref "U10") (pin "84") (pinfunction "VSS_84") (pintype "bidirectional"))
      (node (ref "U10") (pin "92") (pinfunction "VSS_92") (pintype "power_in"))
      (node (ref "U9") (pin "1") (pinfunction "EO_1") (pintype "input"))
      (node (ref "U9") (pin "2") (pinfunction "E1_2") (pintype "input"))
      (node (ref "U9") (pin "3") (pinfunction "E2_3") (pintype "input"))
      (node (ref "U9") (pin "4") (pinfunction "VSS_4") (pintype "power_in"))
      (node (ref "U9") (pin "7") (pinfunction "~{WC}_7") (pintype "input"))
      (node (ref "W1") (pin "2") (pinfunction "C2_2") (pintype "passive"))
    )
    (net (code "94") (name "Net-(BT1-+)") (class "Default")
      (node (ref "BT1") (pin "1") (pinfunction "+_1") (pintype "passive"))
      (node (ref "D14") (pin "3") (pinfunction "A_3") (pintype "passive"))
    )
    (net (code "95") (name "Net-(D6-A)") (class "Default")
      (node (ref "D6") (pin "1") (pinfunction "A_1") (pintype "passive"))
      (node (ref "R82") (pin "1") (pinfunction "1_1") (pintype "passive"))
    )
    (net (code "96") (name "Net-(D15-A)") (class "Default")
      (node (ref "D15") (pin "1") (pinfunction "A_1") (pintype "passive"))
      (node (ref "R42") (pin "1") (pinfunction "1_1") (pintype "passive"))
    )
    (net (code "97") (name "Net-(P21-Pad1)") (class "Default")
      (node (ref "P21") (pin "1") (pinfunction "1_1") (pintype "passive"))
      (node (ref "R76") (pin "2") (pinfunction "2_2") (pintype "passive"))
    )
    (net (code "98") (name "Net-(P21-Pad3)") (class "Default")
      (node (ref "P21") (pin "3") (pinfunction "3_3") (pintype "passive"))
      (node (ref "R77") (pin "2") (pinfunction "2_2") (pintype "passive"))
    )
    (net (code "99") (name "Net-(P21-Pad5)") (class "Default")
      (node (ref "P21") (pin "5") (pinfunction "5_5") (pintype "passive"))
      (node (ref "R78") (pin "2") (pinfunction "2_2") (pintype "passive"))
    )
    (net (code "100") (name "Net-(P21-Pad7)") (class "Default")
      (node (ref "P21") (pin "7") (pinfunction "7_7") (pintype "passive"))
      (node (ref "R79") (pin "2") (pinfunction "2_2") (pintype "passive"))
    )
    (net (code "101") (name "Net-(P21-Pad9)") (class "Default")
      (node (ref "P21") (pin "9") (pinfunction "9_9") (pintype "passive"))
      (node (ref "R80") (pin "2") (pinfunction "2_2") (pintype "passive"))
    )
    (net (code "102") (name "Net-(Q3-D)") (class "Default")
      (node (ref "LS1") (pin "2") (pinfunction "2_2") (pintype "passive"))
      (node (ref "Q3") (pin "3") (pinfunction "D_3") (pintype "passive"))
    )
    (net (code "103") (name "Net-(U10-EBIA6{slash}AN22{slash}RPC1{slash}PMA6{slash}RC1)") (class "Default")
      (node (ref "R42") (pin "2") (pinfunction "2_2") (pintype "passive"))
      (node (ref "U10") (pin "6") (pinfunction "EBIA6/AN22/RPC1/PMA6/RC1_6") (pintype "bidirectional"))
    )
    (net (code "104") (name "Net-(U10-EBIWE{slash}AN20{slash}RPC3{slash}PMWR{slash}RC3)") (class "Default")
      (node (ref "R82") (pin "2") (pinfunction "2_2") (pintype "passive"))
      (node (ref "U10") (pin "8") (pinfunction "EBIWE/AN20/RPC3/PMWR/RC3_8") (pintype "bidirectional"))
    )
    (net (code "105") (name "Net-(U10-OSC1{slash}CLKI{slash}RC12)") (class "Default")
      (node (ref "C35") (pin "1") (pinfunction "1_1") (pintype "passive"))
      (node (ref "R83") (pin "2") (pinfunction "2_2") (pintype "passive"))
      (node (ref "U10") (pin "49") (pinfunction "OSC1/CLKI/RC12_49") (pintype "bidirectional"))
      (node (ref "Y1") (pin "1") (pinfunction "1_1") (pintype "passive"))
    )
    (net (code "106") (name "Net-(U10-OSC2{slash}CLKO{slash}RC15)") (class "Default")
      (node (ref "C45") (pin "1") (pinfunction "1_1") (pintype "passive"))
      (node (ref "R83") (pin "1") (pinfunction "1_1") (pintype "passive"))
      (node (ref "U10") (pin "50") (pinfunction "OSC2/CLKO/RC15_50") (pintype "bidirectional"))
      (node (ref "Y1") (pin "2") (pinfunction "2_2") (pintype "passive"))
    )
    (net (code "107") (name "Net-(U10-SOSCI{slash}RPC13{slash}RC13)") (class "Default")
      (node (ref "C4") (pin "1") (pinfunction "1_1") (pintype "passive"))
      (node (ref "U10") (pin "72") (pinfunction "SOSCI/RPC13/RC13_72") (pintype "bidirectional"))
      (node (ref "Y2") (pin "2") (pinfunction "2_2") (pintype "passive"))
    )
    (net (code "108") (name "Net-(U10-SOSCO{slash}RPC14{slash}T1CK{slash}RC14)") (class "Default")
      (node (ref "C29") (pin "1") (pinfunction "1_1") (pintype "passive"))
      (node (ref "U10") (pin "73") (pinfunction "SOSCO/RPC14/T1CK/RC14_73") (pintype "bidirectional"))
      (node (ref "Y2") (pin "1") (pinfunction "1_1") (pintype "passive"))
    )
    (net (code "109") (name "VCC_32") (class "Default")
      (node (ref "C10") (pin "2") (pinfunction "2_2") (pintype "passive"))
      (node (ref "C11") (pin "2") (pinfunction "2_2") (pintype "passive"))
      (node (ref "C12") (pin "2") (pinfunction "2_2") (pintype "passive"))
      (node (ref "C13") (pin "2") (pinfunction "2_2") (pintype "passive"))
      (node (ref "C21") (pin "2") (pinfunction "2_2") (pintype "passive"))
      (node (ref "C22") (pin "2") (pinfunction "2_2") (pintype "passive"))
      (node (ref "C23") (pin "2") (pinfunction "2_2") (pintype "passive"))
      (node (ref "C25") (pin "2") (pinfunction "2_2") (pintype "passive"))
      (node (ref "C26") (pin "2") (pinfunction "2_2") (pintype "passive"))
      (node (ref "C27") (pin "2") (pinfunction "2_2") (pintype "passive"))
      (node (ref "C28") (pin "2") (pinfunction "2_2") (pintype "passive"))
      (node (ref "C30") (pin "2") (pinfunction "2_2") (pintype "passive"))
      (node (ref "C31") (pin "2") (pinfunction "2_2") (pintype "passive"))
      (node (ref "C32") (pin "2") (pinfunction "2_2") (pintype "passive"))
      (node (ref "C33") (pin "2") (pinfunction "2_2") (pintype "passive"))
      (node (ref "C34") (pin "2") (pinfunction "2_2") (pintype "passive"))
      (node (ref "C6") (pin "2") (pinfunction "2_2") (pintype "passive"))
      (node (ref "C7") (pin "2") (pinfunction "2_2") (pintype "passive"))
      (node (ref "D12") (pin "1") (pinfunction "K1_1") (pintype "passive"))
      (node (ref "D12") (pin "2") (pinfunction "K2_2") (pintype "passive"))
      (node (ref "D14") (pin "1") (pinfunction "K1_1") (pintype "passive"))
      (node (ref "D14") (pin "2") (pinfunction "K2_2") (pintype "passive"))
      (node (ref "P15") (pin "2") (pinfunction "VDD_2") (pintype "passive"))
      (node (ref "P3") (pin "2") (pinfunction "2_2") (pintype "passive"))
      (node (ref "P5") (pin "1") (pinfunction "1_1") (pintype "passive"))
      (node (ref "R75") (pin "2") (pinfunction "2_2") (pintype "passive"))
      (node (ref "U10") (pin "14") (pinfunction "VDD_14") (pintype "power_in"))
      (node (ref "U10") (pin "30") (pinfunction "AVDD_30") (pintype "power_in"))
      (node (ref "U10") (pin "37") (pinfunction "VDD_37") (pintype "power_in"))
      (node (ref "U10") (pin "46") (pinfunction "VDD_46") (pintype "power_in"))
      (node (ref "U10") (pin "52") (pinfunction "VUSB3V3_52") (pintype "bidirectional"))
      (node (ref "U10") (pin "62") (pinfunction "VDD_62") (pintype "power_in"))
      (node (ref "U10") (pin "74") (pinfunction "VDD_74") (pintype "power_in"))
      (node (ref "U10") (pin "83") (pinfunction "VDD_83") (pintype "bidirectional"))
      (node (ref "U10") (pin "93") (pinfunction "VDD_93") (pintype "power_in"))
    )
    (net (code "110") (name "unconnected-(P3-Pad6)") (class "Default")
      (node (ref "P3") (pin "6") (pinfunction "6_6") (pintype "passive+no_connect"))
    )
    (net (code "111") (name "unconnected-(P15-LVP-Pad6)") (class "Default")
      (node (ref "P15") (pin "6") (pinfunction "LVP_6") (pintype "passive+no_connect"))
    )
    (net (code "112") (name "unconnected-(U10-AN45{slash}C1INA{slash}RPB5{slash}RB5-Pad20)") (class "Default")
      (node (ref "U10") (pin "20") (pinfunction "AN45/C1INA/RPB5/RB5_20") (pintype "bidirectional"))
    )
    (net (code "113") (name "unconnected-(U10-EBID0{slash}PMD0{slash}RE0-Pad91)") (class "Default")
      (node (ref "U10") (pin "91") (pinfunction "EBID0/PMD0/RE0_91") (pintype "bidirectional"))
    )
    (net (code "114") (name "unconnected-(U10-EBID10{slash}ETXD0{slash}RPF1{slash}PMD10{slash}RF1-Pad86)") (class "Default")
      (node (ref "U10") (pin "86") (pinfunction "EBID10/ETXD0/RPF1/PMD10/RF1_86") (pintype "bidirectional"))
    )
    (net (code "115") (name "unconnected-(U10-EBID11{slash}ETXD1{slash}RPF0{slash}PMD11{slash}RF0-Pad85)") (class "Default")
      (node (ref "U10") (pin "85") (pinfunction "EBID11/ETXD1/RPF0/PMD11/RF0_85") (pintype "bidirectional"))
    )
    (net (code "116") (name "unconnected-(U10-EBIRDY3{slash}RPF2{slash}SDA3{slash}RF2-Pad57)") (class "Default")
      (node (ref "U10") (pin "57") (pinfunction "EBIRDY3/RPF2/SDA3/RF2_57") (pintype "bidirectional"))
    )
    (net (code "117") (name "unconnected-(U10-TMS{slash}EBIA16{slash}AN24{slash}RA0-Pad17)") (class "Default")
      (node (ref "U10") (pin "17") (pinfunction "TMS/EBIA16/AN24/RA0_17") (pintype "bidirectional"))
    )
  )
)
